# remote_control_light.net
KiCad netlist of a schematic drawn in Altium Designer
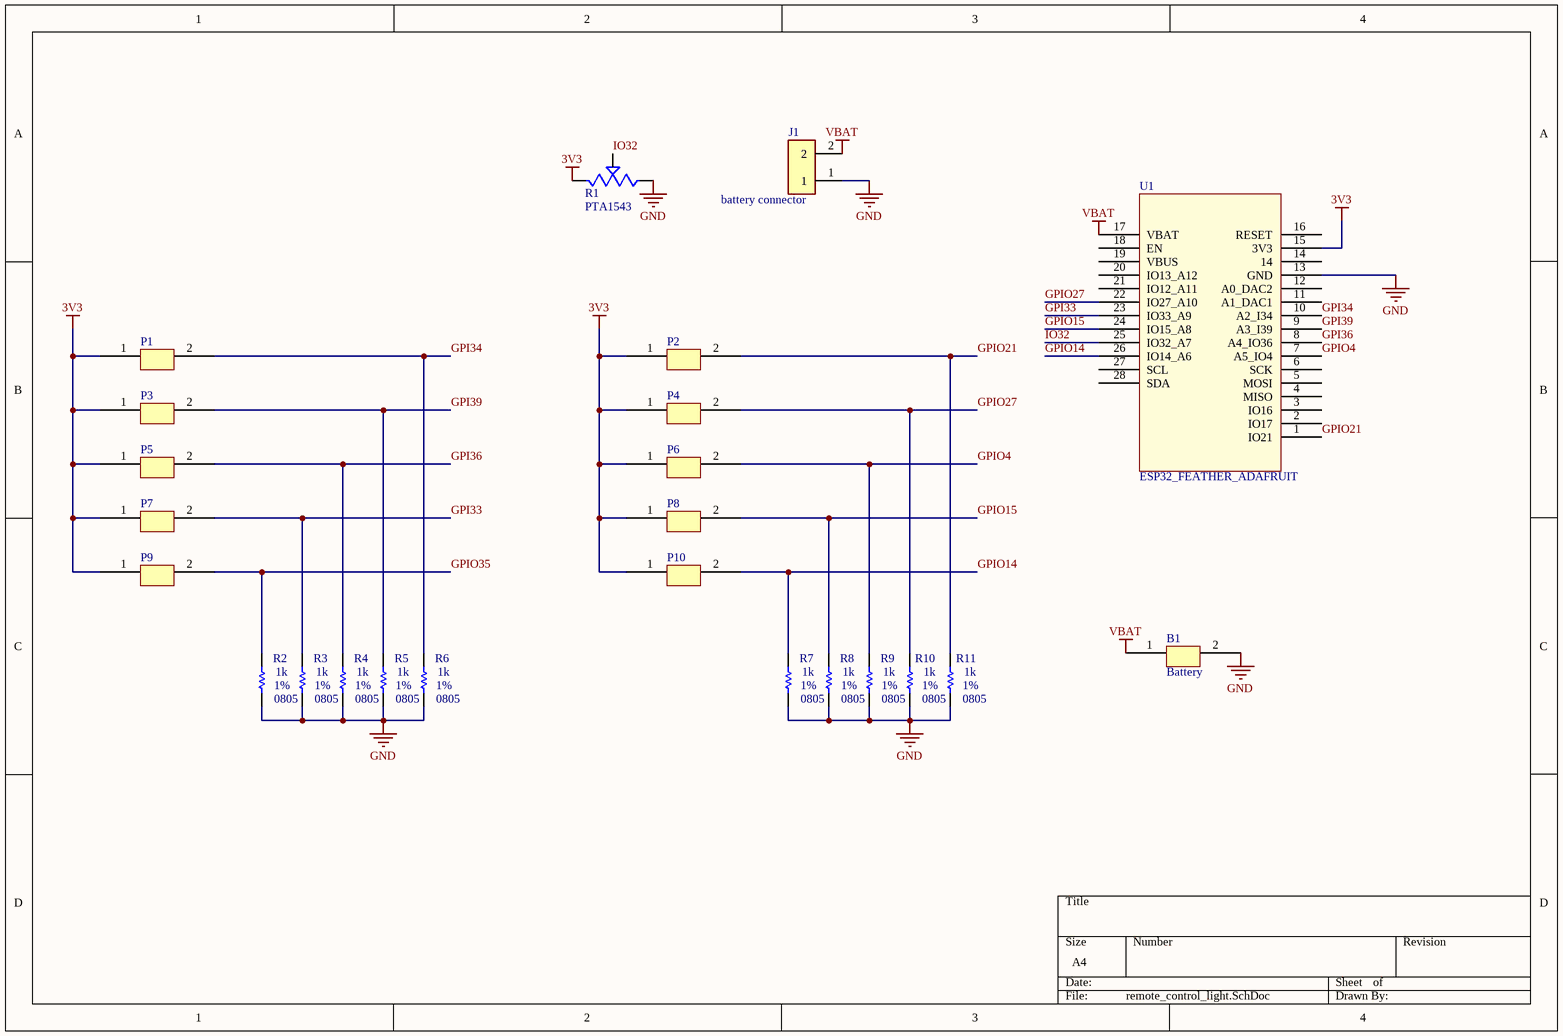
[diagram p0: remote_control_light.SchDoc]

(export (version "E")
  (design (tool "Eeschema 10.0.6"))
  (components
    (comp (ref "B1")
      (value "Battery")
      (footprint "battery-3.7V-1200mAh")
      (libsource (lib "S7CAS_Lib2019_REV1_00") (part "Battery"))
    )
    (comp (ref "J1")
      (value "battery connector")
      (footprint "Battery connector")
      (description "surface mount battery connector")
      (fields (field (name "MP") "1935161") (field (name "MF") "Phoenix Contact"))
      (libsource (lib "S7CAS_Lib2019_REV1_00") (part "CONN_BATT"))
    )
    (comp (ref "P1")
      (value "PUSH_BUTTON_D6F")
      (footprint "PUSH_BUTTON_D6F")
      (libsource (lib "S7CAS_Lib2019_REV1_00") (part "PUSH_BUTTON_D6F"))
    )
    (comp (ref "P2")
      (value "PUSH_BUTTON_D6F")
      (footprint "PUSH_BUTTON_D6F")
      (libsource (lib "S7CAS_Lib2019_REV1_00") (part "PUSH_BUTTON_D6F"))
    )
    (comp (ref "P3")
      (value "PUSH_BUTTON_D6F")
      (footprint "PUSH_BUTTON_D6F")
      (libsource (lib "S7CAS_Lib2019_REV1_00") (part "PUSH_BUTTON_D6F"))
    )
    (comp (ref "P4")
      (value "PUSH_BUTTON_D6F")
      (footprint "PUSH_BUTTON_D6F")
      (libsource (lib "S7CAS_Lib2019_REV1_00") (part "PUSH_BUTTON_D6F"))
    )
    (comp (ref "P5")
      (value "PUSH_BUTTON_D6F")
      (footprint "PUSH_BUTTON_D6F")
      (libsource (lib "S7CAS_Lib2019_REV1_00") (part "PUSH_BUTTON_D6F"))
    )
    (comp (ref "P6")
      (value "PUSH_BUTTON_D6F")
      (footprint "PUSH_BUTTON_D6F")
      (libsource (lib "S7CAS_Lib2019_REV1_00") (part "PUSH_BUTTON_D6F"))
    )
    (comp (ref "P7")
      (value "PUSH_BUTTON_D6F")
      (footprint "PUSH_BUTTON_D6F")
      (libsource (lib "S7CAS_Lib2019_REV1_00") (part "PUSH_BUTTON_D6F"))
    )
    (comp (ref "P8")
      (value "PUSH_BUTTON_D6F")
      (footprint "PUSH_BUTTON_D6F")
      (libsource (lib "S7CAS_Lib2019_REV1_00") (part "PUSH_BUTTON_D6F"))
    )
    (comp (ref "P9")
      (value "PUSH_BUTTON_D6F")
      (footprint "PUSH_BUTTON_D6F")
      (libsource (lib "S7CAS_Lib2019_REV1_00") (part "PUSH_BUTTON_D6F"))
    )
    (comp (ref "P10")
      (value "PUSH_BUTTON_D6F")
      (footprint "PUSH_BUTTON_D6F")
      (libsource (lib "S7CAS_Lib2019_REV1_00") (part "PUSH_BUTTON_D6F"))
    )
    (comp (ref "R1")
      (value "PTA1543")
      (footprint "POT PTA1543")
      (description "10 kOhms 0.05W, 1/20W Through Hole Slide Potentiometer Top Adjustment Type")
      (fields (field (name "DIGI-KEY_PART_NUMBER") "3310P-025-103L-ND") (field (name "MF") "Bourns"))
      (libsource (lib "S7CAS_Lib2019_REV1_00") (part "POT PTA1543"))
    )
    (comp (ref "R2")
      (value "1k")
      (footprint "RES_0805")
      (description "RES - 0805")
      (fields
        (field (name "PACKAGE") "0805")
        (field (name "PRECISION") "1%")
        (field (name "CREATEDBY") "Jonathan Bouchard")
      )
      (libsource (lib "S7CAS_Lib2019_REV1_00") (part "RES - 0805"))
    )
    (comp (ref "R3")
      (value "1k")
      (footprint "RES_0805")
      (description "RES - 0805")
      (fields
        (field (name "PACKAGE") "0805")
        (field (name "PRECISION") "1%")
        (field (name "CREATEDBY") "Jonathan Bouchard")
      )
      (libsource (lib "S7CAS_Lib2019_REV1_00") (part "RES - 0805"))
    )
    (comp (ref "R4")
      (value "1k")
      (footprint "RES_0805")
      (description "RES - 0805")
      (fields
        (field (name "PACKAGE") "0805")
        (field (name "PRECISION") "1%")
        (field (name "CREATEDBY") "Jonathan Bouchard")
      )
      (libsource (lib "S7CAS_Lib2019_REV1_00") (part "RES - 0805"))
    )
    (comp (ref "R5")
      (value "1k")
      (footprint "RES_0805")
      (description "RES - 0805")
      (fields
        (field (name "PACKAGE") "0805")
        (field (name "PRECISION") "1%")
        (field (name "CREATEDBY") "Jonathan Bouchard")
      )
      (libsource (lib "S7CAS_Lib2019_REV1_00") (part "RES - 0805"))
    )
    (comp (ref "R6")
      (value "1k")
      (footprint "RES_0805")
      (description "RES - 0805")
      (fields
        (field (name "PACKAGE") "0805")
        (field (name "PRECISION") "1%")
        (field (name "CREATEDBY") "Jonathan Bouchard")
      )
      (libsource (lib "S7CAS_Lib2019_REV1_00") (part "RES - 0805"))
    )
    (comp (ref "R7")
      (value "1k")
      (footprint "RES_0805")
      (description "RES - 0805")
      (fields
        (field (name "PACKAGE") "0805")
        (field (name "PRECISION") "1%")
        (field (name "CREATEDBY") "Jonathan Bouchard")
      )
      (libsource (lib "S7CAS_Lib2019_REV1_00") (part "RES - 0805"))
    )
    (comp (ref "R8")
      (value "1k")
      (footprint "RES_0805")
      (description "RES - 0805")
      (fields
        (field (name "PACKAGE") "0805")
        (field (name "PRECISION") "1%")
        (field (name "CREATEDBY") "Jonathan Bouchard")
      )
      (libsource (lib "S7CAS_Lib2019_REV1_00") (part "RES - 0805"))
    )
    (comp (ref "R9")
      (value "1k")
      (footprint "RES_0805")
      (description "RES - 0805")
      (fields
        (field (name "PACKAGE") "0805")
        (field (name "PRECISION") "1%")
        (field (name "CREATEDBY") "Jonathan Bouchard")
      )
      (libsource (lib "S7CAS_Lib2019_REV1_00") (part "RES - 0805"))
    )
    (comp (ref "R10")
      (value "1k")
      (footprint "RES_0805")
      (description "RES - 0805")
      (fields
        (field (name "PACKAGE") "0805")
        (field (name "PRECISION") "1%")
        (field (name "CREATEDBY") "Jonathan Bouchard")
      )
      (libsource (lib "S7CAS_Lib2019_REV1_00") (part "RES - 0805"))
    )
    (comp (ref "R11")
      (value "1k")
      (footprint "RES_0805")
      (description "RES - 0805")
      (fields
        (field (name "PACKAGE") "0805")
        (field (name "PRECISION") "1%")
        (field (name "CREATEDBY") "Jonathan Bouchard")
      )
      (libsource (lib "S7CAS_Lib2019_REV1_00") (part "RES - 0805"))
    )
    (comp (ref "U1")
      (value "ESP32_FEATHER_ADAFRUIT")
      (footprint "ESP32_FEATHER")
      (libsource (lib "S7CAS_Lib2019_REV1_00") (part "ESP32_FEATHER_ADAFRUIT"))
    )
  )
  (nets
    (net (code "1") (name "/GPI33") (class "Default")
      (node (ref "P7") (pin "2") (pintype "passive"))
      (node (ref "R3") (pin "2") (pinfunction "2_2") (pintype "passive"))
      (node (ref "U1") (pin "23") (pinfunction "IO33_A9_23") (pintype "passive"))
    )
    (net (code "2") (name "/GPI34") (class "Default")
      (node (ref "P1") (pin "2") (pintype "passive"))
      (node (ref "R6") (pin "2") (pinfunction "2_2") (pintype "passive"))
      (node (ref "U1") (pin "10") (pinfunction "A2_I34_10") (pintype "passive"))
    )
    (net (code "3") (name "/GPI36") (class "Default")
      (node (ref "P5") (pin "2") (pintype "passive"))
      (node (ref "R4") (pin "2") (pinfunction "2_2") (pintype "passive"))
      (node (ref "U1") (pin "8") (pinfunction "A4_IO36_8") (pintype "passive"))
    )
    (net (code "4") (name "/GPI39") (class "Default")
      (node (ref "P3") (pin "2") (pintype "passive"))
      (node (ref "R5") (pin "2") (pinfunction "2_2") (pintype "passive"))
      (node (ref "U1") (pin "9") (pinfunction "A3_I39_9") (pintype "passive"))
    )
    (net (code "5") (name "/GPIO4") (class "Default")
      (node (ref "P6") (pin "2") (pintype "passive"))
      (node (ref "R9") (pin "2") (pinfunction "2_2") (pintype "passive"))
      (node (ref "U1") (pin "7") (pinfunction "A5_IO4_7") (pintype "passive"))
    )
    (net (code "6") (name "/GPIO14") (class "Default")
      (node (ref "P10") (pin "2") (pintype "passive"))
      (node (ref "R7") (pin "2") (pinfunction "2_2") (pintype "passive"))
      (node (ref "U1") (pin "26") (pinfunction "IO14_A6_26") (pintype "passive"))
    )
    (net (code "7") (name "/GPIO15") (class "Default")
      (node (ref "P8") (pin "2") (pintype "passive"))
      (node (ref "R8") (pin "2") (pinfunction "2_2") (pintype "passive"))
      (node (ref "U1") (pin "24") (pinfunction "IO15_A8_24") (pintype "passive"))
    )
    (net (code "8") (name "/GPIO21") (class "Default")
      (node (ref "P2") (pin "2") (pintype "passive"))
      (node (ref "R11") (pin "2") (pinfunction "2_2") (pintype "passive"))
      (node (ref "U1") (pin "1") (pinfunction "IO21_1") (pintype "passive"))
    )
    (net (code "9") (name "/GPIO27") (class "Default")
      (node (ref "P4") (pin "2") (pintype "passive"))
      (node (ref "R10") (pin "2") (pinfunction "2_2") (pintype "passive"))
      (node (ref "U1") (pin "22") (pinfunction "IO27_A10_22") (pintype "passive"))
    )
    (net (code "10") (name "/GPIO35") (class "Default")
      (node (ref "P9") (pin "2") (pintype "passive"))
      (node (ref "R2") (pin "2") (pinfunction "2_2") (pintype "passive"))
    )
    (net (code "11") (name "/IO32") (class "Default")
      (node (ref "R1") (pin "2") (pinfunction "WIPER_2") (pintype "passive"))
      (node (ref "U1") (pin "25") (pinfunction "IO32_A7_25") (pintype "passive"))
    )
    (net (code "12") (name "3V3") (class "Default")
      (node (ref "P1") (pin "1") (pintype "passive"))
      (node (ref "P10") (pin "1") (pintype "passive"))
      (node (ref "P2") (pin "1") (pintype "passive"))
      (node (ref "P3") (pin "1") (pintype "passive"))
      (node (ref "P4") (pin "1") (pintype "passive"))
      (node (ref "P5") (pin "1") (pintype "passive"))
      (node (ref "P6") (pin "1") (pintype "passive"))
      (node (ref "P7") (pin "1") (pintype "passive"))
      (node (ref "P8") (pin "1") (pintype "passive"))
      (node (ref "P9") (pin "1") (pintype "passive"))
      (node (ref "R1") (pin "3") (pinfunction "CW_3") (pintype "passive"))
      (node (ref "U1") (pin "15") (pinfunction "3V3_15") (pintype "passive"))
    )
    (net (code "13") (name "GND") (class "Default")
      (node (ref "B1") (pin "2") (pintype "passive"))
      (node (ref "J1") (pin "1") (pinfunction "1_1") (pintype "passive"))
      (node (ref "R1") (pin "1") (pinfunction "CCW_1") (pintype "passive"))
      (node (ref "R10") (pin "1") (pinfunction "1_1") (pintype "passive"))
      (node (ref "R11") (pin "1") (pinfunction "1_1") (pintype "passive"))
      (node (ref "R2") (pin "1") (pinfunction "1_1") (pintype "passive"))
      (node (ref "R3") (pin "1") (pinfunction "1_1") (pintype "passive"))
      (node (ref "R4") (pin "1") (pinfunction "1_1") (pintype "passive"))
      (node (ref "R5") (pin "1") (pinfunction "1_1") (pintype "passive"))
      (node (ref "R6") (pin "1") (pinfunction "1_1") (pintype "passive"))
      (node (ref "R7") (pin "1") (pinfunction "1_1") (pintype "passive"))
      (node (ref "R8") (pin "1") (pinfunction "1_1") (pintype "passive"))
      (node (ref "R9") (pin "1") (pinfunction "1_1") (pintype "passive"))
      (node (ref "U1") (pin "13") (pinfunction "GND_13") (pintype "passive"))
    )
    (net (code "14") (name "VBAT") (class "Default")
      (node (ref "B1") (pin "1") (pintype "passive"))
      (node (ref "J1") (pin "2") (pinfunction "2_2") (pintype "passive"))
      (node (ref "U1") (pin "17") (pinfunction "VBAT_17") (pintype "passive"))
    )
    (net (code "15") (name "unconnected-(U1-A0_DAC2-Pad12)") (class "Default")
      (node (ref "U1") (pin "12") (pinfunction "A0_DAC2_12") (pintype "passive"))
    )
    (net (code "16") (name "unconnected-(U1-A1_DAC1-Pad11)") (class "Default")
      (node (ref "U1") (pin "11") (pinfunction "A1_DAC1_11") (pintype "passive"))
    )
    (net (code "17") (name "unconnected-(U1-EN-Pad18)") (class "Default")
      (node (ref "U1") (pin "18") (pinfunction "EN_18") (pintype "passive"))
    )
    (net (code "18") (name "unconnected-(U1-IO12_A11-Pad21)") (class "Default")
      (node (ref "U1") (pin "21") (pinfunction "IO12_A11_21") (pintype "passive"))
    )
    (net (code "19") (name "unconnected-(U1-IO13_A12-Pad20)") (class "Default")
      (node (ref "U1") (pin "20") (pinfunction "IO13_A12_20") (pintype "passive"))
    )
    (net (code "20") (name "unconnected-(U1-IO16-Pad3)") (class "Default")
      (node (ref "U1") (pin "3") (pinfunction "IO16_3") (pintype "passive"))
    )
    (net (code "21") (name "unconnected-(U1-IO17-Pad2)") (class "Default")
      (node (ref "U1") (pin "2") (pinfunction "IO17_2") (pintype "passive"))
    )
    (net (code "22") (name "unconnected-(U1-MISO-Pad4)") (class "Default")
      (node (ref "U1") (pin "4") (pinfunction "MISO_4") (pintype "passive"))
    )
    (net (code "23") (name "unconnected-(U1-MOSI-Pad5)") (class "Default")
      (node (ref "U1") (pin "5") (pinfunction "MOSI_5") (pintype "passive"))
    )
    (net (code "24") (name "unconnected-(U1-Pad14)") (class "Default")
      (node (ref "U1") (pin "14") (pinfunction "14_14") (pintype "passive"))
    )
    (net (code "25") (name "unconnected-(U1-RESET-Pad16)") (class "Default")
      (node (ref "U1") (pin "16") (pinfunction "RESET_16") (pintype "passive"))
    )
    (net (code "26") (name "unconnected-(U1-SCK-Pad6)") (class "Default")
      (node (ref "U1") (pin "6") (pinfunction "SCK_6") (pintype "passive"))
    )
    (net (code "27") (name "unconnected-(U1-SCL-Pad27)") (class "Default")
      (node (ref "U1") (pin "27") (pinfunction "SCL_27") (pintype "passive"))
    )
    (net (code "28") (name "unconnected-(U1-SDA-Pad28)") (class "Default")
      (node (ref "U1") (pin "28") (pinfunction "SDA_28") (pintype "passive"))
    )
    (net (code "29") (name "unconnected-(U1-VBUS-Pad19)") (class "Default")
      (node (ref "U1") (pin "19") (pinfunction "VBUS_19") (pintype "passive"))
    )
  )
)
